# plotter.net
KiCad netlist of a schematic drawn in EAGLE
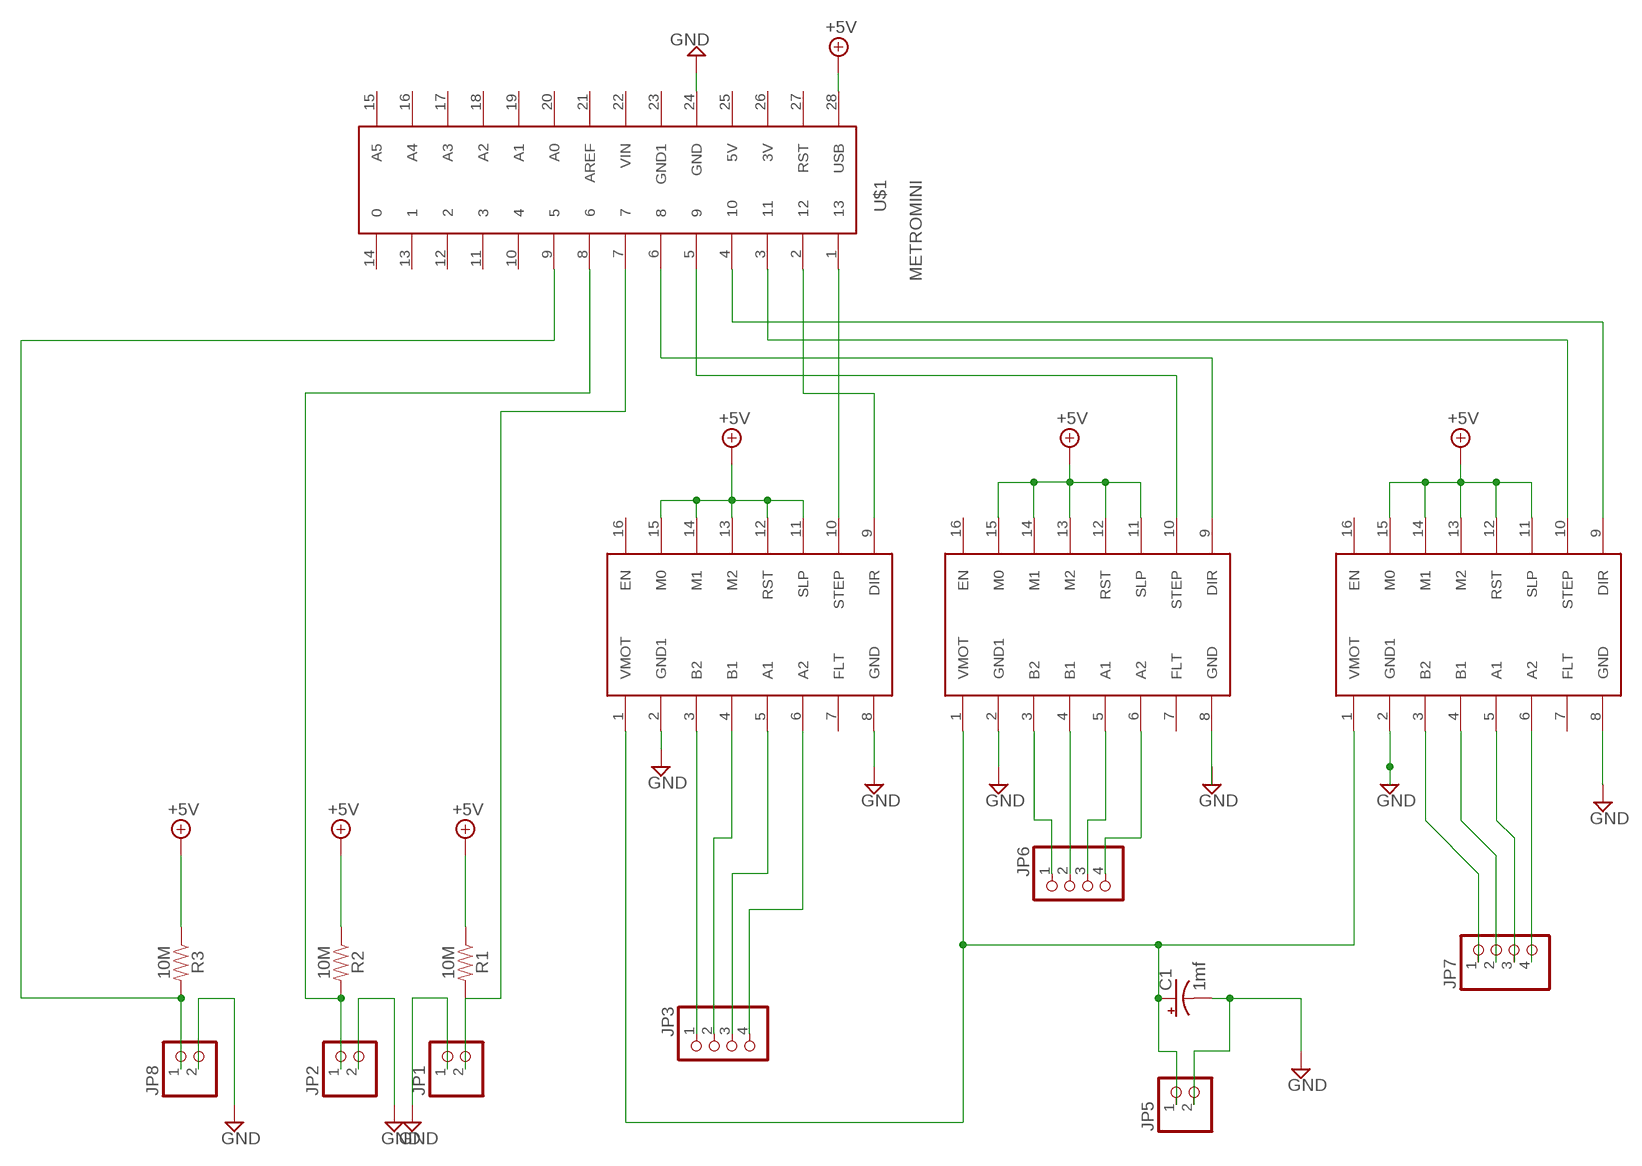
[diagram p0: schematic, sheet 1]

(export (version "E")
  (design (tool "Eeschema 10.0.6"))
  (components
    (comp (ref "C1")
      (value "1mf")
      (footprint "eagle-import:CPOL-RADIAL-5MM-10MM-KIT")
      (libsource (lib "eagle-import") (part "1000UF-RADIAL-5MM-35V-20%-KIT"))
    )
    (comp (ref "JP1")
      (value "PINHD-1X2")
      (footprint "eagle-import:1X02")
      (libsource (lib "eagle-import") (part "PINHD-1X2"))
    )
    (comp (ref "JP2")
      (value "PINHD-1X2")
      (footprint "eagle-import:1X02")
      (libsource (lib "eagle-import") (part "PINHD-1X2"))
    )
    (comp (ref "JP3")
      (value "PINHD-1X4")
      (footprint "eagle-import:1X04")
      (libsource (lib "eagle-import") (part "PINHD-1X4"))
    )
    (comp (ref "JP5")
      (value "PINHD-1X2")
      (footprint "eagle-import:1X02")
      (libsource (lib "eagle-import") (part "PINHD-1X2"))
    )
    (comp (ref "JP6")
      (value "PINHD-1X4")
      (footprint "eagle-import:1X04")
      (libsource (lib "eagle-import") (part "PINHD-1X4"))
    )
    (comp (ref "JP7")
      (value "PINHD-1X4")
      (footprint "eagle-import:1X04")
      (libsource (lib "eagle-import") (part "PINHD-1X4"))
    )
    (comp (ref "JP8")
      (value "PINHD-1X2")
      (footprint "eagle-import:1X02")
      (libsource (lib "eagle-import") (part "PINHD-1X2"))
    )
    (comp (ref "R1")
      (value "10M")
      (footprint "eagle-import:AXIAL-0.3")
      (libsource (lib "eagle-import") (part "10MOHM-HORIZ-1/4W-5%"))
    )
    (comp (ref "R2")
      (value "10M")
      (footprint "eagle-import:AXIAL-0.3")
      (libsource (lib "eagle-import") (part "10MOHM-HORIZ-1/4W-5%"))
    )
    (comp (ref "R3")
      (value "10M")
      (footprint "eagle-import:AXIAL-0.3")
      (libsource (lib "eagle-import") (part "10MOHM-HORIZ-1/4W-5%"))
    )
    (comp (ref "U$1")
      (value "METROMINI")
      (footprint "eagle-import:METROMINI")
      (libsource (lib "eagle-import") (part "METROMINI"))
    )
    (comp (ref "U$2")
      (value "DRV8825")
      (footprint "eagle-import:DRV8825")
      (libsource (lib "eagle-import") (part "DRV8825"))
    )
    (comp (ref "U$3")
      (value "DRV8825")
      (footprint "eagle-import:DRV8825")
      (libsource (lib "eagle-import") (part "DRV8825"))
    )
    (comp (ref "U$4")
      (value "DRV8825")
      (footprint "eagle-import:DRV8825")
      (libsource (lib "eagle-import") (part "DRV8825"))
    )
  )
  (nets
    (net (code "1") (name "+5V") (class "Default")
      (node (ref "R1") (pin "P$1") (pinfunction "1_P$1") (pintype "passive"))
      (node (ref "R2") (pin "P$1") (pinfunction "1_P$1") (pintype "passive"))
      (node (ref "R3") (pin "P$1") (pinfunction "1_P$1") (pintype "passive"))
      (node (ref "U$1") (pin "28") (pinfunction "USB_28") (pintype "bidirectional"))
      (node (ref "U$2") (pin "11") (pinfunction "SLP_11") (pintype "bidirectional"))
      (node (ref "U$2") (pin "12") (pinfunction "RST_12") (pintype "bidirectional"))
      (node (ref "U$2") (pin "13") (pinfunction "M2_13") (pintype "bidirectional"))
      (node (ref "U$2") (pin "14") (pinfunction "M1_14") (pintype "bidirectional"))
      (node (ref "U$2") (pin "15") (pinfunction "M0_15") (pintype "bidirectional"))
      (node (ref "U$3") (pin "11") (pinfunction "SLP_11") (pintype "bidirectional"))
      (node (ref "U$3") (pin "12") (pinfunction "RST_12") (pintype "bidirectional"))
      (node (ref "U$3") (pin "13") (pinfunction "M2_13") (pintype "bidirectional"))
      (node (ref "U$3") (pin "14") (pinfunction "M1_14") (pintype "bidirectional"))
      (node (ref "U$3") (pin "15") (pinfunction "M0_15") (pintype "bidirectional"))
      (node (ref "U$4") (pin "11") (pinfunction "SLP_11") (pintype "bidirectional"))
      (node (ref "U$4") (pin "12") (pinfunction "RST_12") (pintype "bidirectional"))
      (node (ref "U$4") (pin "13") (pinfunction "M2_13") (pintype "bidirectional"))
      (node (ref "U$4") (pin "14") (pinfunction "M1_14") (pintype "bidirectional"))
      (node (ref "U$4") (pin "15") (pinfunction "M0_15") (pintype "bidirectional"))
    )
    (net (code "2") (name "GND") (class "Default")
      (node (ref "C1") (pin "-") (pinfunction "-_-") (pintype "passive"))
      (node (ref "JP1") (pin "1") (pinfunction "1_1") (pintype "passive"))
      (node (ref "JP2") (pin "2") (pinfunction "2_2") (pintype "passive"))
      (node (ref "JP5") (pin "2") (pinfunction "2_2") (pintype "passive"))
      (node (ref "JP8") (pin "2") (pinfunction "2_2") (pintype "passive"))
      (node (ref "U$1") (pin "24") (pinfunction "GND_24") (pintype "bidirectional"))
      (node (ref "U$2") (pin "2") (pinfunction "GND1_2") (pintype "bidirectional"))
      (node (ref "U$2") (pin "8") (pinfunction "GND_8") (pintype "bidirectional"))
      (node (ref "U$3") (pin "2") (pinfunction "GND1_2") (pintype "bidirectional"))
      (node (ref "U$3") (pin "8") (pinfunction "GND_8") (pintype "bidirectional"))
      (node (ref "U$4") (pin "2") (pinfunction "GND1_2") (pintype "bidirectional"))
      (node (ref "U$4") (pin "8") (pinfunction "GND_8") (pintype "bidirectional"))
    )
    (net (code "3") (name "Net-(R1-2)") (class "Default")
      (node (ref "JP1") (pin "2") (pinfunction "2_2") (pintype "passive"))
      (node (ref "R1") (pin "P$2") (pinfunction "2_P$2") (pintype "passive"))
      (node (ref "U$1") (pin "7") (pinfunction "7_7") (pintype "bidirectional"))
    )
    (net (code "4") (name "Net-(R2-2)") (class "Default")
      (node (ref "JP2") (pin "1") (pinfunction "1_1") (pintype "passive"))
      (node (ref "R2") (pin "P$2") (pinfunction "2_P$2") (pintype "passive"))
      (node (ref "U$1") (pin "8") (pinfunction "6_8") (pintype "bidirectional"))
    )
    (net (code "5") (name "Net-(R3-2)") (class "Default")
      (node (ref "JP8") (pin "1") (pinfunction "1_1") (pintype "passive"))
      (node (ref "R3") (pin "P$2") (pinfunction "2_P$2") (pintype "passive"))
      (node (ref "U$1") (pin "9") (pinfunction "5_9") (pintype "bidirectional"))
    )
    (net (code "6") (name "Net-(U$1-8)") (class "Default")
      (node (ref "U$1") (pin "6") (pinfunction "8_6") (pintype "bidirectional"))
      (node (ref "U$2") (pin "9") (pinfunction "DIR_9") (pintype "bidirectional"))
    )
    (net (code "7") (name "Net-(U$1-9)") (class "Default")
      (node (ref "U$1") (pin "5") (pinfunction "9_5") (pintype "bidirectional"))
      (node (ref "U$2") (pin "10") (pinfunction "STEP_10") (pintype "bidirectional"))
    )
    (net (code "8") (name "Net-(U$1-10)") (class "Default")
      (node (ref "U$1") (pin "4") (pinfunction "10_4") (pintype "bidirectional"))
      (node (ref "U$3") (pin "9") (pinfunction "DIR_9") (pintype "bidirectional"))
    )
    (net (code "9") (name "Net-(U$1-11)") (class "Default")
      (node (ref "U$1") (pin "3") (pinfunction "11_3") (pintype "bidirectional"))
      (node (ref "U$3") (pin "10") (pinfunction "STEP_10") (pintype "bidirectional"))
    )
    (net (code "10") (name "Net-(U$1-12)") (class "Default")
      (node (ref "U$1") (pin "2") (pinfunction "12_2") (pintype "bidirectional"))
      (node (ref "U$4") (pin "9") (pinfunction "DIR_9") (pintype "bidirectional"))
    )
    (net (code "11") (name "Net-(U$1-13)") (class "Default")
      (node (ref "U$1") (pin "1") (pinfunction "13_1") (pintype "bidirectional"))
      (node (ref "U$4") (pin "10") (pinfunction "STEP_10") (pintype "bidirectional"))
    )
    (net (code "12") (name "Net-(U$2-A1)") (class "Default")
      (node (ref "JP6") (pin "3") (pinfunction "3_3") (pintype "passive"))
      (node (ref "U$2") (pin "5") (pinfunction "A1_5") (pintype "bidirectional"))
    )
    (net (code "13") (name "Net-(U$2-A2)") (class "Default")
      (node (ref "JP6") (pin "4") (pinfunction "4_4") (pintype "passive"))
      (node (ref "U$2") (pin "6") (pinfunction "A2_6") (pintype "bidirectional"))
    )
    (net (code "14") (name "Net-(U$2-B1)") (class "Default")
      (node (ref "JP6") (pin "2") (pinfunction "2_2") (pintype "passive"))
      (node (ref "U$2") (pin "4") (pinfunction "B1_4") (pintype "bidirectional"))
    )
    (net (code "15") (name "Net-(U$2-B2)") (class "Default")
      (node (ref "JP6") (pin "1") (pinfunction "1_1") (pintype "passive"))
      (node (ref "U$2") (pin "3") (pinfunction "B2_3") (pintype "bidirectional"))
    )
    (net (code "16") (name "Net-(U$2-VMOT)") (class "Default")
      (node (ref "C1") (pin "+") (pinfunction "+_+") (pintype "passive"))
      (node (ref "JP5") (pin "1") (pinfunction "1_1") (pintype "passive"))
      (node (ref "U$2") (pin "1") (pinfunction "VMOT_1") (pintype "bidirectional"))
      (node (ref "U$3") (pin "1") (pinfunction "VMOT_1") (pintype "bidirectional"))
      (node (ref "U$4") (pin "1") (pinfunction "VMOT_1") (pintype "bidirectional"))
    )
    (net (code "17") (name "Net-(U$3-A1)") (class "Default")
      (node (ref "JP7") (pin "3") (pinfunction "3_3") (pintype "passive"))
      (node (ref "U$3") (pin "5") (pinfunction "A1_5") (pintype "bidirectional"))
    )
    (net (code "18") (name "Net-(U$3-A2)") (class "Default")
      (node (ref "JP7") (pin "4") (pinfunction "4_4") (pintype "passive"))
      (node (ref "U$3") (pin "6") (pinfunction "A2_6") (pintype "bidirectional"))
    )
    (net (code "19") (name "Net-(U$3-B1)") (class "Default")
      (node (ref "JP7") (pin "2") (pinfunction "2_2") (pintype "passive"))
      (node (ref "U$3") (pin "4") (pinfunction "B1_4") (pintype "bidirectional"))
    )
    (net (code "20") (name "Net-(U$3-B2)") (class "Default")
      (node (ref "JP7") (pin "1") (pinfunction "1_1") (pintype "passive"))
      (node (ref "U$3") (pin "3") (pinfunction "B2_3") (pintype "bidirectional"))
    )
    (net (code "21") (name "Net-(U$4-A1)") (class "Default")
      (node (ref "JP3") (pin "3") (pinfunction "3_3") (pintype "passive"))
      (node (ref "U$4") (pin "5") (pinfunction "A1_5") (pintype "bidirectional"))
    )
    (net (code "22") (name "Net-(U$4-A2)") (class "Default")
      (node (ref "JP3") (pin "4") (pinfunction "4_4") (pintype "passive"))
      (node (ref "U$4") (pin "6") (pinfunction "A2_6") (pintype "bidirectional"))
    )
    (net (code "23") (name "Net-(U$4-B1)") (class "Default")
      (node (ref "JP3") (pin "2") (pinfunction "2_2") (pintype "passive"))
      (node (ref "U$4") (pin "4") (pinfunction "B1_4") (pintype "bidirectional"))
    )
    (net (code "24") (name "Net-(U$4-B2)") (class "Default")
      (node (ref "JP3") (pin "1") (pinfunction "1_1") (pintype "passive"))
      (node (ref "U$4") (pin "3") (pinfunction "B2_3") (pintype "bidirectional"))
    )
    (net (code "25") (name "unconnected-(U$1-0-Pad14)") (class "Default")
      (node (ref "U$1") (pin "14") (pinfunction "0_14") (pintype "bidirectional"))
    )
    (net (code "26") (name "unconnected-(U$1-1-Pad13)") (class "Default")
      (node (ref "U$1") (pin "13") (pinfunction "1_13") (pintype "bidirectional"))
    )
    (net (code "27") (name "unconnected-(U$1-2-Pad12)") (class "Default")
      (node (ref "U$1") (pin "12") (pinfunction "2_12") (pintype "bidirectional"))
    )
    (net (code "28") (name "unconnected-(U$1-3-Pad11)") (class "Default")
      (node (ref "U$1") (pin "11") (pinfunction "3_11") (pintype "bidirectional"))
    )
    (net (code "29") (name "unconnected-(U$1-3V-Pad26)") (class "Default")
      (node (ref "U$1") (pin "26") (pinfunction "3V_26") (pintype "bidirectional"))
    )
    (net (code "30") (name "unconnected-(U$1-4-Pad10)") (class "Default")
      (node (ref "U$1") (pin "10") (pinfunction "4_10") (pintype "bidirectional"))
    )
    (net (code "31") (name "unconnected-(U$1-5V-Pad25)") (class "Default")
      (node (ref "U$1") (pin "25") (pinfunction "5V_25") (pintype "bidirectional"))
    )
    (net (code "32") (name "unconnected-(U$1-A0-Pad20)") (class "Default")
      (node (ref "U$1") (pin "20") (pinfunction "A0_20") (pintype "bidirectional"))
    )
    (net (code "33") (name "unconnected-(U$1-A1-Pad19)") (class "Default")
      (node (ref "U$1") (pin "19") (pinfunction "A1_19") (pintype "bidirectional"))
    )
    (net (code "34") (name "unconnected-(U$1-A2-Pad18)") (class "Default")
      (node (ref "U$1") (pin "18") (pinfunction "A2_18") (pintype "bidirectional"))
    )
    (net (code "35") (name "unconnected-(U$1-A3-Pad17)") (class "Default")
      (node (ref "U$1") (pin "17") (pinfunction "A3_17") (pintype "bidirectional"))
    )
    (net (code "36") (name "unconnected-(U$1-A4-Pad16)") (class "Default")
      (node (ref "U$1") (pin "16") (pinfunction "A4_16") (pintype "bidirectional"))
    )
    (net (code "37") (name "unconnected-(U$1-A5-Pad15)") (class "Default")
      (node (ref "U$1") (pin "15") (pinfunction "A5_15") (pintype "bidirectional"))
    )
    (net (code "38") (name "unconnected-(U$1-AREF-Pad21)") (class "Default")
      (node (ref "U$1") (pin "21") (pinfunction "AREF_21") (pintype "bidirectional"))
    )
    (net (code "39") (name "unconnected-(U$1-GND1-Pad23)") (class "Default")
      (node (ref "U$1") (pin "23") (pinfunction "GND1_23") (pintype "bidirectional"))
    )
    (net (code "40") (name "unconnected-(U$1-RST-Pad27)") (class "Default")
      (node (ref "U$1") (pin "27") (pinfunction "RST_27") (pintype "bidirectional"))
    )
    (net (code "41") (name "unconnected-(U$1-VIN-Pad22)") (class "Default")
      (node (ref "U$1") (pin "22") (pinfunction "VIN_22") (pintype "bidirectional"))
    )
    (net (code "42") (name "unconnected-(U$2-EN-Pad16)") (class "Default")
      (node (ref "U$2") (pin "16") (pinfunction "EN_16") (pintype "bidirectional"))
    )
    (net (code "43") (name "unconnected-(U$2-FLT-Pad7)") (class "Default")
      (node (ref "U$2") (pin "7") (pinfunction "FLT_7") (pintype "bidirectional"))
    )
    (net (code "44") (name "unconnected-(U$3-EN-Pad16)") (class "Default")
      (node (ref "U$3") (pin "16") (pinfunction "EN_16") (pintype "bidirectional"))
    )
    (net (code "45") (name "unconnected-(U$3-FLT-Pad7)") (class "Default")
      (node (ref "U$3") (pin "7") (pinfunction "FLT_7") (pintype "bidirectional"))
    )
    (net (code "46") (name "unconnected-(U$4-EN-Pad16)") (class "Default")
      (node (ref "U$4") (pin "16") (pinfunction "EN_16") (pintype "bidirectional"))
    )
    (net (code "47") (name "unconnected-(U$4-FLT-Pad7)") (class "Default")
      (node (ref "U$4") (pin "7") (pinfunction "FLT_7") (pintype "bidirectional"))
    )
  )
)
